# DM1092_LEVEL_SHIFT.net
KiCad netlist of a schematic drawn in Altium Designer
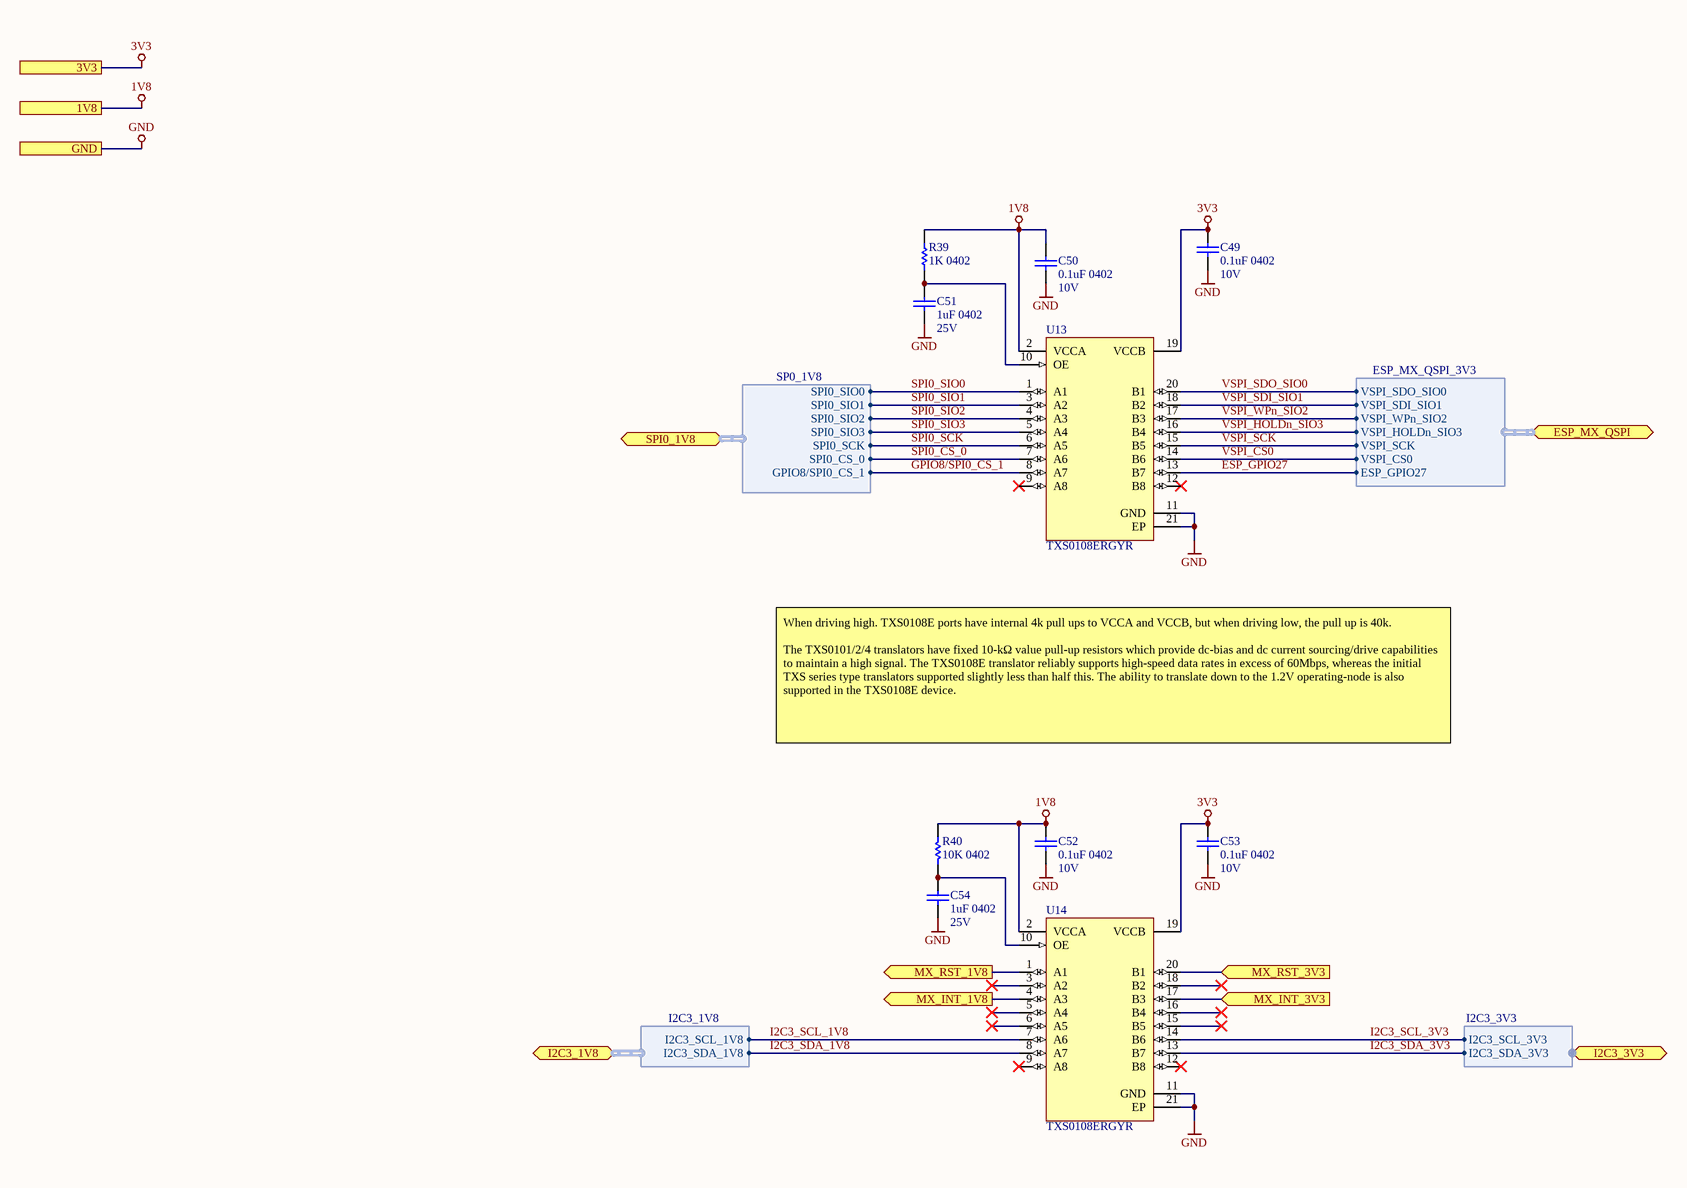
[diagram p0: DM1092_LEVEL_SHIFT.SchDoc]

(export (version "E")
  (design (tool "Eeschema 10.0.6"))
  (components
    (comp (ref "C49")
      (value "0.1uF 0402")
      (footprint "CAP_Altium_Vault_Generic:CAPC0402(1005)70_N")
      (description "CAP CER 0.1UF 10V X7R 0402 5%")
      (fields (field (name "TOLERANCE") "5%") (field (name "VOLTAGE RATING") "10V"))
      (libsource (lib "LuxonisMaster") (part "GRM155R71A104JA01D"))
    )
    (comp (ref "C50")
      (value "0.1uF 0402")
      (footprint "CAP_Altium_Vault_Generic:CAPC0402(1005)70_N")
      (description "CAP CER 0.1UF 10V X7R 0402 5%")
      (fields (field (name "TOLERANCE") "5%") (field (name "VOLTAGE RATING") "10V"))
      (libsource (lib "LuxonisMaster") (part "GRM155R71A104JA01D"))
    )
    (comp (ref "C51")
      (value "1uF 0402")
      (footprint "CAP_Altium_Vault_Generic:CAPC0402(1005)70_N")
      (description "CAP CER 1UF 25V X5R 0402 10%")
      (fields
        (field (name "TOLERANCE") "10%")
        (field (name "VOLTAGE") "25V")
        (field (name "VOLTAGE RATING") "25V")
      )
      (libsource (lib "LuxonisMaster") (part "GRM155R61E105KA12D"))
    )
    (comp (ref "C52")
      (value "0.1uF 0402")
      (footprint "CAP_Altium_Vault_Generic:CAPC0402(1005)70_N")
      (description "CAP CER 0.1UF 10V X7R 0402 5%")
      (fields (field (name "TOLERANCE") "5%") (field (name "VOLTAGE RATING") "10V"))
      (libsource (lib "LuxonisMaster") (part "GRM155R71A104JA01D"))
    )
    (comp (ref "C53")
      (value "0.1uF 0402")
      (footprint "CAP_Altium_Vault_Generic:CAPC0402(1005)70_N")
      (description "CAP CER 0.1UF 10V X7R 0402 5%")
      (fields (field (name "TOLERANCE") "5%") (field (name "VOLTAGE RATING") "10V"))
      (libsource (lib "LuxonisMaster") (part "GRM155R71A104JA01D"))
    )
    (comp (ref "C54")
      (value "1uF 0402")
      (footprint "CAP_Altium_Vault_Generic:CAPC0402(1005)70_N")
      (description "CAP CER 1UF 25V X5R 0402 10%")
      (fields
        (field (name "TOLERANCE") "10%")
        (field (name "VOLTAGE") "25V")
        (field (name "VOLTAGE RATING") "25V")
      )
      (libsource (lib "LuxonisMaster") (part "GRM155R61E105KA12D"))
    )
    (comp (ref "R39")
      (value "1K 0402")
      (footprint "RES_Altium_Vault_Generic:RESC0402(1005)_N")
      (fields (field (name "TOLERANCE") "1%"))
      (libsource (lib "LuxonisMaster") (part "RC0402FR-071KL"))
    )
    (comp (ref "R40")
      (value "10K 0402")
      (footprint "RES_Altium_Vault_Generic:RESC0402(1005)_N")
      (fields (field (name "TOLERANCE") "1%"))
      (libsource (lib "LuxonisMaster") (part "RC0402FR-1310KL"))
    )
    (comp (ref "U13")
      (value "TXS0108ERGYR")
      (footprint "LuxonisMaster:TXS0108ERGYR")
      (description "IC TRNSLTR BIDIRECTIONAL 20VQFN")
      (libsource (lib "LuxonisMaster") (part "TXS0108ERGYR"))
    )
    (comp (ref "U14")
      (value "TXS0108ERGYR")
      (footprint "LuxonisMaster:TXS0108ERGYR")
      (description "IC TRNSLTR BIDIRECTIONAL 20VQFN")
      (libsource (lib "LuxonisMaster") (part "TXS0108ERGYR"))
    )
  )
  (nets
    (net (code "5") (name "/ESP_GPIO27") (class "Default")
      (node (ref "U13") (pin "13") (pinfunction "B7_13") (pintype "bidirectional"))
    )
    (net (code "6") (name "/GPIO8{slash}SPI0_CS_1") (class "Default")
      (node (ref "U13") (pin "8") (pinfunction "A7_8") (pintype "bidirectional"))
    )
    (net (code "7") (name "/I2C3_SCL_1V8") (class "Default")
      (node (ref "U14") (pin "7") (pinfunction "A6_7") (pintype "bidirectional"))
    )
    (net (code "8") (name "/I2C3_SCL_3V3") (class "Default")
      (node (ref "U14") (pin "14") (pinfunction "B6_14") (pintype "bidirectional"))
    )
    (net (code "9") (name "/I2C3_SDA_1V8") (class "Default")
      (node (ref "U14") (pin "8") (pinfunction "A7_8") (pintype "bidirectional"))
    )
    (net (code "10") (name "/I2C3_SDA_3V3") (class "Default")
      (node (ref "U14") (pin "13") (pinfunction "B7_13") (pintype "bidirectional"))
    )
    (net (code "11") (name "/MX_INT_1V8") (class "Default")
      (node (ref "U14") (pin "4") (pinfunction "A3_4") (pintype "bidirectional"))
    )
    (net (code "12") (name "/MX_INT_3V3") (class "Default")
      (node (ref "U14") (pin "17") (pinfunction "B3_17") (pintype "bidirectional"))
    )
    (net (code "13") (name "/MX_RST_1V8") (class "Default")
      (node (ref "U14") (pin "1") (pinfunction "A1_1") (pintype "bidirectional"))
    )
    (net (code "14") (name "/MX_RST_3V3") (class "Default")
      (node (ref "U14") (pin "20") (pinfunction "B1_20") (pintype "bidirectional"))
    )
    (net (code "15") (name "/SPI0_CS_0") (class "Default")
      (node (ref "U13") (pin "7") (pinfunction "A6_7") (pintype "bidirectional"))
    )
    (net (code "16") (name "/SPI0_SCK") (class "Default")
      (node (ref "U13") (pin "6") (pinfunction "A5_6") (pintype "bidirectional"))
    )
    (net (code "17") (name "/SPI0_SIO0") (class "Default")
      (node (ref "U13") (pin "1") (pinfunction "A1_1") (pintype "bidirectional"))
    )
    (net (code "18") (name "/SPI0_SIO1") (class "Default")
      (node (ref "U13") (pin "3") (pinfunction "A2_3") (pintype "bidirectional"))
    )
    (net (code "19") (name "/SPI0_SIO2") (class "Default")
      (node (ref "U13") (pin "4") (pinfunction "A3_4") (pintype "bidirectional"))
    )
    (net (code "20") (name "/SPI0_SIO3") (class "Default")
      (node (ref "U13") (pin "5") (pinfunction "A4_5") (pintype "bidirectional"))
    )
    (net (code "21") (name "/VSPI_CS0") (class "Default")
      (node (ref "U13") (pin "14") (pinfunction "B6_14") (pintype "bidirectional"))
    )
    (net (code "22") (name "/VSPI_HOLDn_SIO3") (class "Default")
      (node (ref "U13") (pin "16") (pinfunction "B4_16") (pintype "bidirectional"))
    )
    (net (code "23") (name "/VSPI_SCK") (class "Default")
      (node (ref "U13") (pin "15") (pinfunction "B5_15") (pintype "bidirectional"))
    )
    (net (code "24") (name "/VSPI_SDI_SIO1") (class "Default")
      (node (ref "U13") (pin "18") (pinfunction "B2_18") (pintype "bidirectional"))
    )
    (net (code "25") (name "/VSPI_SDO_SIO0") (class "Default")
      (node (ref "U13") (pin "20") (pinfunction "B1_20") (pintype "bidirectional"))
    )
    (net (code "26") (name "/VSPI_WPn_SIO2") (class "Default")
      (node (ref "U13") (pin "17") (pinfunction "B3_17") (pintype "bidirectional"))
    )
    (net (code "31") (name "1V8") (class "Default")
      (node (ref "C50") (pin "2") (pinfunction "2_2") (pintype "passive"))
      (node (ref "C52") (pin "2") (pinfunction "2_2") (pintype "passive"))
      (node (ref "R39") (pin "2") (pinfunction "2_2") (pintype "passive"))
      (node (ref "R40") (pin "1") (pinfunction "1_1") (pintype "passive"))
      (node (ref "U13") (pin "2") (pinfunction "VCCA_2") (pintype "power_in"))
      (node (ref "U14") (pin "2") (pinfunction "VCCA_2") (pintype "power_in"))
    )
    (net (code "32") (name "3V3") (class "Default")
      (node (ref "C49") (pin "2") (pinfunction "2_2") (pintype "passive"))
      (node (ref "C53") (pin "2") (pinfunction "2_2") (pintype "passive"))
      (node (ref "U13") (pin "19") (pinfunction "VCCB_19") (pintype "power_in"))
      (node (ref "U14") (pin "19") (pinfunction "VCCB_19") (pintype "power_in"))
    )
    (net (code "33") (name "GND") (class "Default")
      (node (ref "C49") (pin "1") (pinfunction "1_1") (pintype "passive"))
      (node (ref "C50") (pin "1") (pinfunction "1_1") (pintype "passive"))
      (node (ref "C51") (pin "1") (pinfunction "1_1") (pintype "passive"))
      (node (ref "C52") (pin "1") (pinfunction "1_1") (pintype "passive"))
      (node (ref "C53") (pin "1") (pinfunction "1_1") (pintype "passive"))
      (node (ref "C54") (pin "1") (pinfunction "1_1") (pintype "passive"))
      (node (ref "U13") (pin "11") (pinfunction "GND_11") (pintype "power_in"))
      (node (ref "U13") (pin "21") (pinfunction "EP_21") (pintype "power_in"))
      (node (ref "U14") (pin "11") (pinfunction "GND_11") (pintype "power_in"))
      (node (ref "U14") (pin "21") (pinfunction "EP_21") (pintype "power_in"))
    )
    (net (code "34") (name "Net-(U13-OE)") (class "Default")
      (node (ref "C51") (pin "2") (pinfunction "2_2") (pintype "passive"))
      (node (ref "R39") (pin "1") (pinfunction "1_1") (pintype "passive"))
      (node (ref "U13") (pin "10") (pinfunction "OE_10") (pintype "input"))
    )
    (net (code "35") (name "Net-(U14-OE)") (class "Default")
      (node (ref "C54") (pin "2") (pinfunction "2_2") (pintype "passive"))
      (node (ref "R40") (pin "2") (pinfunction "2_2") (pintype "passive"))
      (node (ref "U14") (pin "10") (pinfunction "OE_10") (pintype "input"))
    )
    (net (code "36") (name "unconnected-(U13-A8-Pad9)") (class "Default")
      (node (ref "U13") (pin "9") (pinfunction "A8_9") (pintype "bidirectional+no_connect"))
    )
    (net (code "37") (name "unconnected-(U13-B8-Pad12)") (class "Default")
      (node (ref "U13") (pin "12") (pinfunction "B8_12") (pintype "bidirectional+no_connect"))
    )
    (net (code "38") (name "unconnected-(U14-A2-Pad3)") (class "Default")
      (node (ref "U14") (pin "3") (pinfunction "A2_3") (pintype "bidirectional+no_connect"))
    )
    (net (code "39") (name "unconnected-(U14-A4-Pad5)") (class "Default")
      (node (ref "U14") (pin "5") (pinfunction "A4_5") (pintype "bidirectional+no_connect"))
    )
    (net (code "40") (name "unconnected-(U14-A5-Pad6)") (class "Default")
      (node (ref "U14") (pin "6") (pinfunction "A5_6") (pintype "bidirectional+no_connect"))
    )
    (net (code "41") (name "unconnected-(U14-A8-Pad9)") (class "Default")
      (node (ref "U14") (pin "9") (pinfunction "A8_9") (pintype "bidirectional+no_connect"))
    )
    (net (code "42") (name "unconnected-(U14-B2-Pad18)") (class "Default")
      (node (ref "U14") (pin "18") (pinfunction "B2_18") (pintype "bidirectional+no_connect"))
    )
    (net (code "43") (name "unconnected-(U14-B4-Pad16)") (class "Default")
      (node (ref "U14") (pin "16") (pinfunction "B4_16") (pintype "bidirectional+no_connect"))
    )
    (net (code "44") (name "unconnected-(U14-B5-Pad15)") (class "Default")
      (node (ref "U14") (pin "15") (pinfunction "B5_15") (pintype "bidirectional+no_connect"))
    )
    (net (code "45") (name "unconnected-(U14-B8-Pad12)") (class "Default")
      (node (ref "U14") (pin "12") (pinfunction "B8_12") (pintype "bidirectional+no_connect"))
    )
  )
)
